# Item.net
KiCad netlist of a schematic drawn in Altium Designer
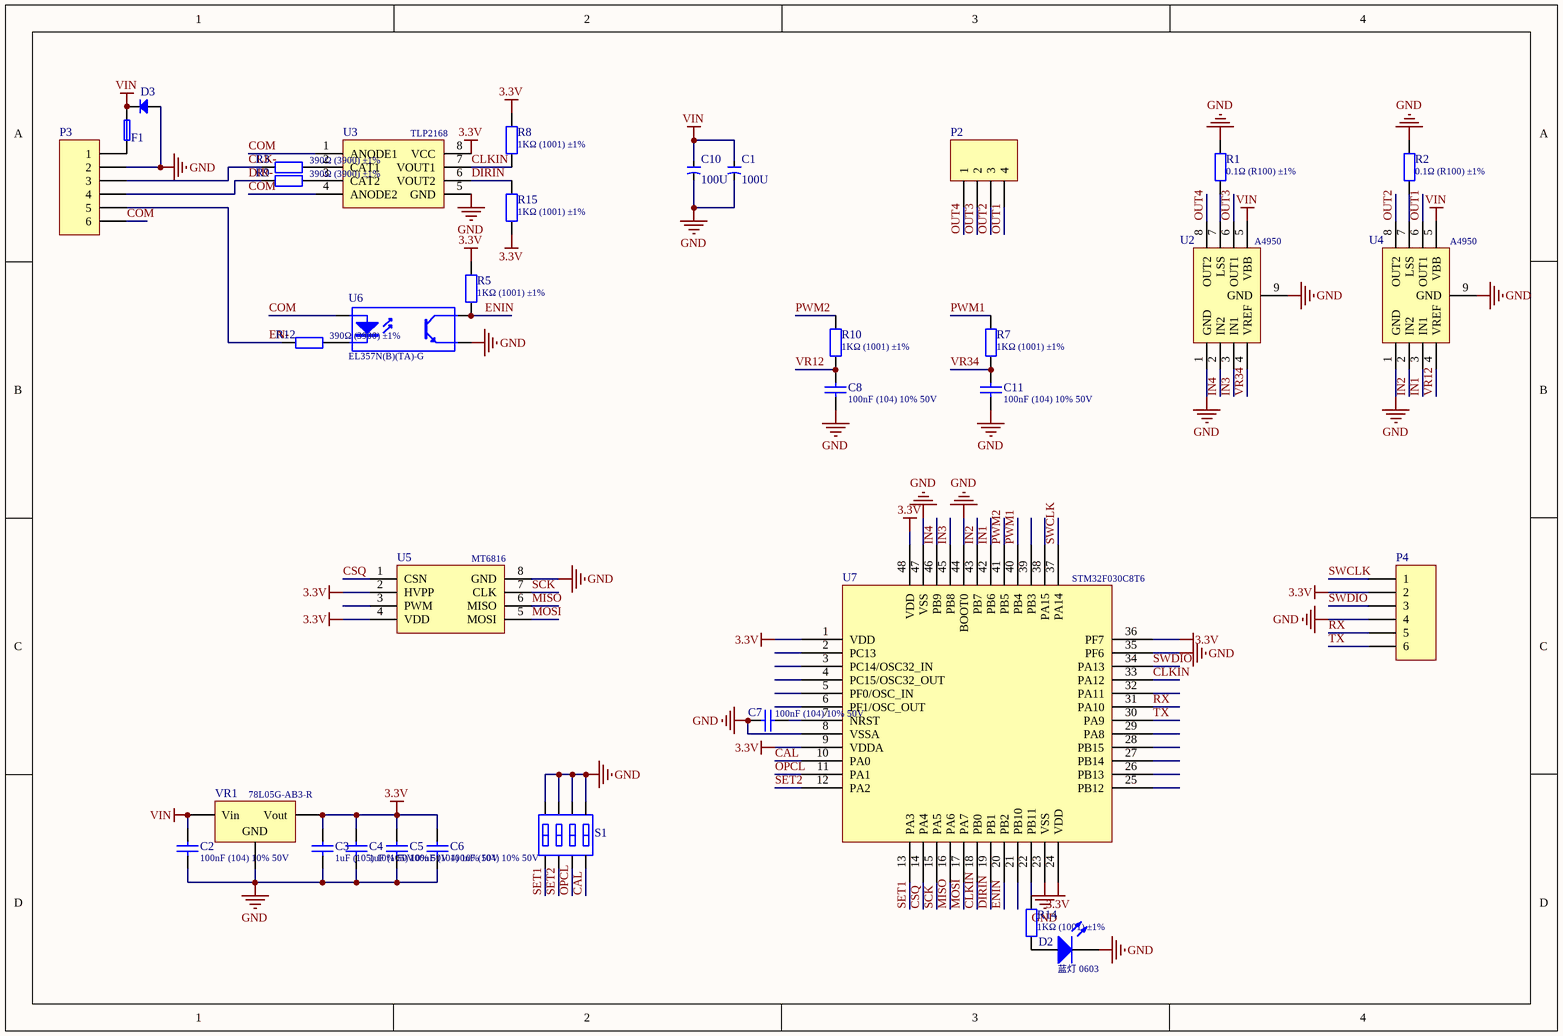
[diagram p0: Item.SchDoc]

(export (version "E")
  (design (tool "Eeschema 10.0.6"))
  (components
    (comp (ref "C1")
      (value "100U")
      (footprint "CAP6377")
      (description "Polarized Capacitor (Axial)")
      (fields (field (name "Comment") "CAP POL") (field (name "PUBLISHER") "Altium Limited"))
      (libsource (lib "MySchib") (part "CAP POL"))
    )
    (comp (ref "C2")
      (value "100nF (104) 10% 50V")
      (footprint "0603_C")
      (description "贴片电容")
      (libsource (lib "Miscellaneous Devices LC") (part "0603 100nF (104) 10% 50V"))
    )
    (comp (ref "C3")
      (value "1uF (105) 10% 50V")
      (footprint "0603_C")
      (description "贴片电容")
      (libsource (lib "Miscellaneous Devices LC") (part "0603 1uF (105) 10% 50V"))
    )
    (comp (ref "C4")
      (value "1uF (105) 10% 50V")
      (footprint "0603_C")
      (description "贴片电容")
      (libsource (lib "Miscellaneous Devices LC") (part "0603 1uF (105) 10% 50V"))
    )
    (comp (ref "C5")
      (value "100nF (104) 10% 50V")
      (footprint "0603_C")
      (description "贴片电容")
      (libsource (lib "Miscellaneous Devices LC") (part "0603 100nF (104) 10% 50V"))
    )
    (comp (ref "C6")
      (value "100nF (104) 10% 50V")
      (footprint "0603_C")
      (description "贴片电容")
      (libsource (lib "Miscellaneous Devices LC") (part "0603 100nF (104) 10% 50V"))
    )
    (comp (ref "C7")
      (value "100nF (104) 10% 50V")
      (footprint "0603_C")
      (description "贴片电容")
      (libsource (lib "Miscellaneous Devices LC") (part "0603 100nF (104) 10% 50V"))
    )
    (comp (ref "C8")
      (value "100nF (104) 10% 50V")
      (footprint "0603_C")
      (description "贴片电容")
      (libsource (lib "Miscellaneous Devices LC") (part "0603 100nF (104) 10% 50V"))
    )
    (comp (ref "C10")
      (value "100U")
      (footprint "CAP6377")
      (description "Polarized Capacitor (Axial)")
      (fields (field (name "Comment") "CAP POL") (field (name "PUBLISHER") "Altium Limited"))
      (libsource (lib "MySchib") (part "CAP POL"))
    )
    (comp (ref "C11")
      (value "100nF (104) 10% 50V")
      (footprint "0603_C")
      (description "贴片电容")
      (libsource (lib "Miscellaneous Devices LC") (part "0603 100nF (104) 10% 50V"))
    )
    (comp (ref "D2")
      (value "蓝灯 0603")
      (footprint "0603_LED_S1")
      (description "发光二极管")
      (libsource (lib "Miscellaneous Devices LC") (part "0603 蓝灯"))
    )
    (comp (ref "D3")
      (value "DIODE")
      (footprint "SOD-123")
      (description "Diode")
      (fields (field (name "PUBLISHER") "Altium Limited"))
      (libsource (lib "MySchib") (part "DIODE"))
    )
    (comp (ref "F1")
      (value "FUSE")
      (footprint "1206_R")
      (description "Fuse")
      (fields (field (name "PUBLISHER") "Altium Limited"))
      (libsource (lib "MySchib") (part "FUSE"))
    )
    (comp (ref "P2")
      (value "HEADER4")
      (footprint "XH-4-S-2")
      (description "Header, 4-Pin")
      (fields (field (name "PUBLISHER") "Altium Limited"))
      (libsource (lib "MySchib") (part "HEADER4"))
    )
    (comp (ref "P3")
      (value "HEADER6")
      (footprint "XH-6-S")
      (description "Header, 6-Pin")
      (fields (field (name "PUBLISHER") "Altium Limited"))
      (libsource (lib "MySchib") (part "HEADER6"))
    )
    (comp (ref "P4")
      (value "HEADER6")
      (footprint "6P-1.27MM")
      (description "Header, 6-Pin")
      (fields (field (name "PUBLISHER") "Altium Limited"))
      (libsource (lib "") (part "HEADER6_1"))
    )
    (comp (ref "R1")
      (value "0.1Ω (R100) ±1%")
      (footprint "1206_R")
      (description "贴片电阻")
      (libsource (lib "Miscellaneous Devices LC") (part "1206 0.1Ω (R100) 1%"))
    )
    (comp (ref "R2")
      (value "0.1Ω (R100) ±1%")
      (footprint "1206_R")
      (description "贴片电阻")
      (libsource (lib "Miscellaneous Devices LC") (part "1206 0.1Ω (R100) 1%"))
    )
    (comp (ref "R3")
      (value "390Ω (3900) ±1%")
      (footprint "0603_R")
      (description "贴片电阻")
      (libsource (lib "Miscellaneous Devices LC") (part "0603 390Ω (3900) 1%"))
    )
    (comp (ref "R5")
      (value "1KΩ (1001) ±1%")
      (footprint "0603_R")
      (description "贴片电阻")
      (libsource (lib "Miscellaneous Devices LC") (part "0603 1KΩ (1001) 1%"))
    )
    (comp (ref "R7")
      (value "1KΩ (1001) ±1%")
      (footprint "0603_R")
      (description "贴片电阻")
      (libsource (lib "Miscellaneous Devices LC") (part "0603 1KΩ (1001) 1%"))
    )
    (comp (ref "R8")
      (value "1KΩ (1001) ±1%")
      (footprint "0603_R")
      (description "贴片电阻")
      (libsource (lib "Miscellaneous Devices LC") (part "0603 1KΩ (1001) 1%"))
    )
    (comp (ref "R9")
      (value "390Ω (3900) ±1%")
      (footprint "0603_R")
      (description "贴片电阻")
      (libsource (lib "Miscellaneous Devices LC") (part "0603 390Ω (3900) 1%"))
    )
    (comp (ref "R10")
      (value "1KΩ (1001) ±1%")
      (footprint "0603_R")
      (description "贴片电阻")
      (libsource (lib "Miscellaneous Devices LC") (part "0603 1KΩ (1001) 1%"))
    )
    (comp (ref "R12")
      (value "390Ω (3900) ±1%")
      (footprint "0603_R")
      (description "贴片电阻")
      (libsource (lib "Miscellaneous Devices LC") (part "0603 390Ω (3900) 1%"))
    )
    (comp (ref "R14")
      (value "1KΩ (1001) ±1%")
      (footprint "0603_R")
      (description "贴片电阻")
      (libsource (lib "Miscellaneous Devices LC") (part "0603 1KΩ (1001) 1%"))
    )
    (comp (ref "R15")
      (value "1KΩ (1001) ±1%")
      (footprint "0603_R")
      (description "贴片电阻")
      (libsource (lib "Miscellaneous Devices LC") (part "0603 1KΩ (1001) 1%"))
    )
    (comp (ref "S1")
      (value "SWDIP-4")
      (footprint "SWSUR-4")
      (description "DIP Switch, 4Position, SPST")
      (fields (field (name "PUBLISHER") "Altium Limited"))
      (libsource (lib "MySchib") (part "SWDIP-4"))
    )
    (comp (ref "U2")
      (value "A4950")
      (footprint "SOIC-8_A4950")
      (description "Dual Full-Bridge  DMOS PWM Motor Driver")
      (libsource (lib "MySchib") (part "A4950"))
    )
    (comp (ref "U3")
      (value "TLP2168")
      (footprint "SO-8_3.9mm")
      (description "HIGH SPEED 10MBit/s LOGIC GATE  PHOTOCOUPLER")
      (libsource (lib "MySchib") (part "TLP2168"))
    )
    (comp (ref "U4")
      (value "A4950")
      (footprint "SOIC-8_A4950")
      (description "Dual Full-Bridge  DMOS PWM Motor Driver")
      (libsource (lib "MySchib") (part "A4950"))
    )
    (comp (ref "U5")
      (value "MT6816")
      (footprint "PG-DSO-8S")
      (description "GMR-Based Angle Sensor")
      (libsource (lib "MySchib") (part "MT6816"))
    )
    (comp (ref "U6")
      (value "EL357N(B)(TA)-G")
      (footprint "SOP-4_P2.54")
      (description "贴片光耦")
      (libsource (lib "Miscellaneous Devices LC") (part "EL357N(B)(TA)-G_[C6649]"))
    )
    (comp (ref "U7")
      (value "STM32F030C8T6")
      (footprint "LQFP-48_7x7x05P")
      (description "ARM")
      (libsource (lib "Miscellaneous Devices LC") (part "STM32F030C8T6"))
    )
    (comp (ref "VR1")
      (value "78L05G-AB3-R")
      (footprint "SOT-89(SOT-89-3)")
      (description "低压差线性稳压(LDO)")
      (libsource (lib "Miscellaneous Devices LC") (part "SOT-89 78L05G-AB3-R"))
    )
  )
  (nets
    (net (code "1") (name "/CAL") (class "Default")
      (node (ref "S1") (pin "7") (pinfunction "A4_7") (pintype "passive"))
      (node (ref "U7") (pin "10") (pinfunction "PA0_10") (pintype "passive"))
    )
    (net (code "2") (name "/CLK-") (class "Default")
      (node (ref "P3") (pin "3") (pinfunction "3_3") (pintype "passive"))
      (node (ref "R3") (pin "1") (pinfunction "1_1") (pintype "passive"))
    )
    (net (code "3") (name "/CLKIN") (class "Default")
      (node (ref "R8") (pin "1") (pinfunction "1_1") (pintype "passive"))
      (node (ref "U3") (pin "7") (pinfunction "VOUT1_7") (pintype "passive"))
      (node (ref "U7") (pin "18") (pinfunction "PB0_18") (pintype "passive"))
      (node (ref "U7") (pin "33") (pinfunction "PA12_33") (pintype "passive"))
    )
    (net (code "4") (name "/COM") (class "Default")
      (node (ref "P3") (pin "6") (pinfunction "6_6") (pintype "passive"))
      (node (ref "U3") (pin "1") (pinfunction "ANODE1_1") (pintype "passive"))
      (node (ref "U3") (pin "4") (pinfunction "ANODE2_4") (pintype "passive"))
      (node (ref "U6") (pin "1") (pinfunction "A_1") (pintype "passive"))
    )
    (net (code "5") (name "/CSQ") (class "Default")
      (node (ref "U5") (pin "1") (pinfunction "CSN_1") (pintype "passive"))
      (node (ref "U7") (pin "14") (pinfunction "PA4_14") (pintype "passive"))
    )
    (net (code "6") (name "/DIR-") (class "Default")
      (node (ref "P3") (pin "4") (pinfunction "4_4") (pintype "passive"))
      (node (ref "R9") (pin "1") (pinfunction "1_1") (pintype "passive"))
    )
    (net (code "7") (name "/DIRIN") (class "Default")
      (node (ref "R15") (pin "2") (pinfunction "2_2") (pintype "passive"))
      (node (ref "U3") (pin "6") (pinfunction "VOUT2_6") (pintype "passive"))
      (node (ref "U7") (pin "19") (pinfunction "PB1_19") (pintype "passive"))
    )
    (net (code "8") (name "/EN-") (class "Default")
      (node (ref "P3") (pin "5") (pinfunction "5_5") (pintype "passive"))
      (node (ref "R12") (pin "1") (pinfunction "1_1") (pintype "passive"))
    )
    (net (code "9") (name "/ENIN") (class "Default")
      (node (ref "R5") (pin "1") (pinfunction "1_1") (pintype "passive"))
      (node (ref "U6") (pin "4") (pinfunction "C_4") (pintype "passive"))
      (node (ref "U7") (pin "20") (pinfunction "PB2_20") (pintype "passive"))
    )
    (net (code "10") (name "/IN1") (class "Default")
      (node (ref "U4") (pin "3") (pinfunction "IN1_3") (pintype "passive"))
      (node (ref "U7") (pin "42") (pinfunction "PB6_42") (pintype "passive"))
    )
    (net (code "11") (name "/IN2") (class "Default")
      (node (ref "U4") (pin "2") (pinfunction "IN2_2") (pintype "passive"))
      (node (ref "U7") (pin "43") (pinfunction "PB7_43") (pintype "passive"))
    )
    (net (code "12") (name "/IN3") (class "Default")
      (node (ref "U2") (pin "3") (pinfunction "IN1_3") (pintype "passive"))
      (node (ref "U7") (pin "45") (pinfunction "PB8_45") (pintype "passive"))
    )
    (net (code "13") (name "/IN4") (class "Default")
      (node (ref "U2") (pin "2") (pinfunction "IN2_2") (pintype "passive"))
      (node (ref "U7") (pin "46") (pinfunction "PB9_46") (pintype "passive"))
    )
    (net (code "14") (name "/MISO") (class "Default")
      (node (ref "U5") (pin "6") (pinfunction "MISO_6") (pintype "passive"))
      (node (ref "U7") (pin "16") (pinfunction "PA6_16") (pintype "passive"))
    )
    (net (code "15") (name "/MOSI") (class "Default")
      (node (ref "U5") (pin "5") (pinfunction "MOSI_5") (pintype "passive"))
      (node (ref "U7") (pin "17") (pinfunction "PA7_17") (pintype "passive"))
    )
    (net (code "16") (name "/OPCL") (class "Default")
      (node (ref "S1") (pin "5") (pinfunction "A3_5") (pintype "passive"))
      (node (ref "U7") (pin "11") (pinfunction "PA1_11") (pintype "passive"))
    )
    (net (code "17") (name "/OUT1") (class "Default")
      (node (ref "P2") (pin "4") (pinfunction "4_4") (pintype "passive"))
      (node (ref "U4") (pin "6") (pinfunction "OUT1_6") (pintype "passive"))
    )
    (net (code "18") (name "/OUT2") (class "Default")
      (node (ref "P2") (pin "3") (pinfunction "3_3") (pintype "passive"))
      (node (ref "U4") (pin "8") (pinfunction "OUT2_8") (pintype "passive"))
    )
    (net (code "19") (name "/OUT3") (class "Default")
      (node (ref "P2") (pin "2") (pinfunction "2_2") (pintype "passive"))
      (node (ref "U2") (pin "6") (pinfunction "OUT1_6") (pintype "passive"))
    )
    (net (code "20") (name "/OUT4") (class "Default")
      (node (ref "P2") (pin "1") (pinfunction "1_1") (pintype "passive"))
      (node (ref "U2") (pin "8") (pinfunction "OUT2_8") (pintype "passive"))
    )
    (net (code "21") (name "/PWM1") (class "Default")
      (node (ref "R7") (pin "2") (pinfunction "2_2") (pintype "passive"))
      (node (ref "U7") (pin "40") (pinfunction "PB4_40") (pintype "passive"))
    )
    (net (code "22") (name "/PWM2") (class "Default")
      (node (ref "R10") (pin "2") (pinfunction "2_2") (pintype "passive"))
      (node (ref "U7") (pin "41") (pinfunction "PB5_41") (pintype "passive"))
    )
    (net (code "23") (name "/RX") (class "Default")
      (node (ref "P4") (pin "5") (pinfunction "5_5") (pintype "passive"))
      (node (ref "U7") (pin "31") (pinfunction "PA10_31") (pintype "passive"))
    )
    (net (code "24") (name "/SCK") (class "Default")
      (node (ref "U5") (pin "7") (pinfunction "CLK_7") (pintype "passive"))
      (node (ref "U7") (pin "15") (pinfunction "PA5_15") (pintype "passive"))
    )
    (net (code "25") (name "/SET1") (class "Default")
      (node (ref "S1") (pin "1") (pinfunction "A1_1") (pintype "passive"))
      (node (ref "U7") (pin "13") (pinfunction "PA3_13") (pintype "passive"))
    )
    (net (code "26") (name "/SET2") (class "Default")
      (node (ref "S1") (pin "3") (pinfunction "A2_3") (pintype "passive"))
      (node (ref "U7") (pin "12") (pinfunction "PA2_12") (pintype "passive"))
    )
    (net (code "27") (name "/SWCLK") (class "Default")
      (node (ref "P4") (pin "1") (pinfunction "1_1") (pintype "passive"))
      (node (ref "U7") (pin "37") (pinfunction "PA14_37") (pintype "passive"))
    )
    (net (code "28") (name "/SWDIO") (class "Default")
      (node (ref "P4") (pin "3") (pinfunction "3_3") (pintype "passive"))
      (node (ref "U7") (pin "34") (pinfunction "PA13_34") (pintype "passive"))
    )
    (net (code "29") (name "/TX") (class "Default")
      (node (ref "P4") (pin "6") (pinfunction "6_6") (pintype "passive"))
      (node (ref "U7") (pin "30") (pinfunction "PA9_30") (pintype "passive"))
    )
    (net (code "30") (name "/VR12") (class "Default")
      (node (ref "C8") (pin "2") (pinfunction "2_2") (pintype "passive"))
      (node (ref "R10") (pin "1") (pinfunction "1_1") (pintype "passive"))
      (node (ref "U4") (pin "4") (pinfunction "VREF_4") (pintype "passive"))
    )
    (net (code "31") (name "/VR34") (class "Default")
      (node (ref "C11") (pin "2") (pinfunction "2_2") (pintype "passive"))
      (node (ref "R7") (pin "1") (pinfunction "1_1") (pintype "passive"))
      (node (ref "U2") (pin "4") (pinfunction "VREF_4") (pintype "passive"))
    )
    (net (code "32") (name "3.3V") (class "Default")
      (node (ref "C3") (pin "2") (pinfunction "2_2") (pintype "passive"))
      (node (ref "C4") (pin "2") (pinfunction "2_2") (pintype "passive"))
      (node (ref "C5") (pin "1") (pinfunction "1_1") (pintype "passive"))
      (node (ref "C6") (pin "1") (pinfunction "1_1") (pintype "passive"))
      (node (ref "P4") (pin "2") (pinfunction "2_2") (pintype "passive"))
      (node (ref "R15") (pin "1") (pinfunction "1_1") (pintype "passive"))
      (node (ref "R5") (pin "2") (pinfunction "2_2") (pintype "passive"))
      (node (ref "R8") (pin "2") (pinfunction "2_2") (pintype "passive"))
      (node (ref "U3") (pin "8") (pinfunction "VCC_8") (pintype "passive"))
      (node (ref "U5") (pin "2") (pinfunction "HVPP_2") (pintype "passive"))
      (node (ref "U5") (pin "4") (pinfunction "VDD_4") (pintype "passive"))
      (node (ref "U7") (pin "1") (pinfunction "VDD_1") (pintype "passive"))
      (node (ref "U7") (pin "24") (pinfunction "VDD_24") (pintype "passive"))
      (node (ref "U7") (pin "36") (pinfunction "PF7_36") (pintype "passive"))
      (node (ref "U7") (pin "48") (pinfunction "VDD_48") (pintype "passive"))
      (node (ref "U7") (pin "9") (pinfunction "VDDA_9") (pintype "passive"))
      (node (ref "VR1") (pin "1") (pinfunction "Vout_1") (pintype "passive"))
    )
    (net (code "33") (name "GND") (class "Default")
      (node (ref "C1") (pin "2") (pinfunction "2_2") (pintype "passive"))
      (node (ref "C10") (pin "2") (pinfunction "2_2") (pintype "passive"))
      (node (ref "C11") (pin "1") (pinfunction "1_1") (pintype "passive"))
      (node (ref "C2") (pin "2") (pinfunction "2_2") (pintype "passive"))
      (node (ref "C3") (pin "1") (pinfunction "1_1") (pintype "passive"))
      (node (ref "C4") (pin "1") (pinfunction "1_1") (pintype "passive"))
      (node (ref "C5") (pin "2") (pinfunction "2_2") (pintype "passive"))
      (node (ref "C6") (pin "2") (pinfunction "2_2") (pintype "passive"))
      (node (ref "C7") (pin "2") (pinfunction "2_2") (pintype "passive"))
      (node (ref "C8") (pin "1") (pinfunction "1_1") (pintype "passive"))
      (node (ref "D2") (pin "K") (pinfunction "K_K") (pintype "passive"))
      (node (ref "D3") (pin "1") (pinfunction "A_1") (pintype "passive"))
      (node (ref "P3") (pin "2") (pinfunction "2_2") (pintype "passive"))
      (node (ref "P4") (pin "4") (pinfunction "4_4") (pintype "passive"))
      (node (ref "R1") (pin "1") (pinfunction "1_1") (pintype "passive"))
      (node (ref "R2") (pin "1") (pinfunction "1_1") (pintype "passive"))
      (node (ref "S1") (pin "2") (pinfunction "B1_2") (pintype "passive"))
      (node (ref "S1") (pin "4") (pinfunction "B2_4") (pintype "passive"))
      (node (ref "S1") (pin "6") (pinfunction "B3_6") (pintype "passive"))
      (node (ref "S1") (pin "8") (pinfunction "B4_8") (pintype "passive"))
      (node (ref "U2") (pin "1") (pinfunction "GND_1") (pintype "passive"))
      (node (ref "U2") (pin "9") (pinfunction "GND_9") (pintype "passive"))
      (node (ref "U3") (pin "5") (pinfunction "GND_5") (pintype "passive"))
      (node (ref "U4") (pin "1") (pinfunction "GND_1") (pintype "passive"))
      (node (ref "U4") (pin "9") (pinfunction "GND_9") (pintype "passive"))
      (node (ref "U5") (pin "8") (pinfunction "GND_8") (pintype "passive"))
      (node (ref "U6") (pin "3") (pinfunction "E_3") (pintype "passive"))
      (node (ref "U7") (pin "23") (pinfunction "VSS_23") (pintype "passive"))
      (node (ref "U7") (pin "35") (pinfunction "PF6_35") (pintype "passive"))
      (node (ref "U7") (pin "44") (pinfunction "BOOT0_44") (pintype "passive"))
      (node (ref "U7") (pin "47") (pinfunction "VSS_47") (pintype "passive"))
      (node (ref "U7") (pin "8") (pinfunction "VSSA_8") (pintype "passive"))
      (node (ref "VR1") (pin "2") (pinfunction "GND_2") (pintype "passive"))
    )
    (net (code "34") (name "Net-(D2-PadA)") (class "Default")
      (node (ref "D2") (pin "A") (pinfunction "A_A") (pintype "passive"))
      (node (ref "R14") (pin "1") (pinfunction "1_1") (pintype "passive"))
    )
    (net (code "35") (name "Net-(F1-Pad1)") (class "Default")
      (node (ref "F1") (pin "1") (pinfunction "1_1") (pintype "passive"))
      (node (ref "P3") (pin "1") (pinfunction "1_1") (pintype "passive"))
    )
    (net (code "36") (name "Net-(U2-LSS)") (class "Default")
      (node (ref "R1") (pin "2") (pinfunction "2_2") (pintype "passive"))
      (node (ref "U2") (pin "7") (pinfunction "LSS_7") (pintype "passive"))
    )
    (net (code "37") (name "Net-(U3-CAT1)") (class "Default")
      (node (ref "R3") (pin "2") (pinfunction "2_2") (pintype "passive"))
      (node (ref "U3") (pin "2") (pinfunction "CAT1_2") (pintype "passive"))
    )
    (net (code "38") (name "Net-(U3-CAT2)") (class "Default")
      (node (ref "R9") (pin "2") (pinfunction "2_2") (pintype "passive"))
      (node (ref "U3") (pin "3") (pinfunction "CAT2_3") (pintype "passive"))
    )
    (net (code "39") (name "Net-(U4-LSS)") (class "Default")
      (node (ref "R2") (pin "2") (pinfunction "2_2") (pintype "passive"))
      (node (ref "U4") (pin "7") (pinfunction "LSS_7") (pintype "passive"))
    )
    (net (code "40") (name "Net-(U6-K)") (class "Default")
      (node (ref "R12") (pin "2") (pinfunction "2_2") (pintype "passive"))
      (node (ref "U6") (pin "2") (pinfunction "K_2") (pintype "passive"))
    )
    (net (code "41") (name "Net-(U7-NRST)") (class "Default")
      (node (ref "C7") (pin "1") (pinfunction "1_1") (pintype "passive"))
      (node (ref "U7") (pin "7") (pinfunction "NRST_7") (pintype "passive"))
    )
    (net (code "42") (name "Net-(U7-PB11)") (class "Default")
      (node (ref "R14") (pin "2") (pinfunction "2_2") (pintype "passive"))
      (node (ref "U7") (pin "22") (pinfunction "PB11_22") (pintype "passive"))
    )
    (net (code "43") (name "VIN") (class "Default")
      (node (ref "C1") (pin "1") (pinfunction "1_1") (pintype "passive"))
      (node (ref "C10") (pin "1") (pinfunction "1_1") (pintype "passive"))
      (node (ref "C2") (pin "1") (pinfunction "1_1") (pintype "passive"))
      (node (ref "D3") (pin "2") (pinfunction "K_2") (pintype "passive"))
      (node (ref "F1") (pin "2") (pinfunction "2_2") (pintype "passive"))
      (node (ref "U2") (pin "5") (pinfunction "VBB_5") (pintype "passive"))
      (node (ref "U4") (pin "5") (pinfunction "VBB_5") (pintype "passive"))
      (node (ref "VR1") (pin "3") (pinfunction "Vin_3") (pintype "passive"))
    )
    (net (code "44") (name "unconnected-(U5-PWM-Pad3)") (class "Default")
      (node (ref "U5") (pin "3") (pinfunction "PWM_3") (pintype "passive"))
    )
    (net (code "45") (name "unconnected-(U7-PA8-Pad29)") (class "Default")
      (node (ref "U7") (pin "29") (pinfunction "PA8_29") (pintype "passive"))
    )
    (net (code "46") (name "unconnected-(U7-PA11-Pad32)") (class "Default")
      (node (ref "U7") (pin "32") (pinfunction "PA11_32") (pintype "passive"))
    )
    (net (code "47") (name "unconnected-(U7-PA15-Pad38)") (class "Default")
      (node (ref "U7") (pin "38") (pinfunction "PA15_38") (pintype "passive"))
    )
    (net (code "48") (name "unconnected-(U7-PB3-Pad39)") (class "Default")
      (node (ref "U7") (pin "39") (pinfunction "PB3_39") (pintype "passive"))
    )
    (net (code "49") (name "unconnected-(U7-PB10-Pad21)") (class "Default")
      (node (ref "U7") (pin "21") (pinfunction "PB10_21") (pintype "passive"))
    )
    (net (code "50") (name "unconnected-(U7-PB12-Pad25)") (class "Default")
      (node (ref "U7") (pin "25") (pinfunction "PB12_25") (pintype "passive"))
    )
    (net (code "51") (name "unconnected-(U7-PB13-Pad26)") (class "Default")
      (node (ref "U7") (pin "26") (pinfunction "PB13_26") (pintype "passive"))
    )
    (net (code "52") (name "unconnected-(U7-PB14-Pad27)") (class "Default")
      (node (ref "U7") (pin "27") (pinfunction "PB14_27") (pintype "passive"))
    )
    (net (code "53") (name "unconnected-(U7-PB15-Pad28)") (class "Default")
      (node (ref "U7") (pin "28") (pinfunction "PB15_28") (pintype "passive"))
    )
    (net (code "54") (name "unconnected-(U7-PC13-Pad2)") (class "Default")
      (node (ref "U7") (pin "2") (pinfunction "PC13_2") (pintype "passive"))
    )
    (net (code "55") (name "unconnected-(U7-PC14{slash}OSC32_IN-Pad3)") (class "Default")
      (node (ref "U7") (pin "3") (pinfunction "PC14/OSC32_IN_3") (pintype "passive"))
    )
    (net (code "56") (name "unconnected-(U7-PC15{slash}OSC32_OUT-Pad4)") (class "Default")
      (node (ref "U7") (pin "4") (pinfunction "PC15/OSC32_OUT_4") (pintype "passive"))
    )
    (net (code "57") (name "unconnected-(U7-PF0{slash}OSC_IN-Pad5)") (class "Default")
      (node (ref "U7") (pin "5") (pinfunction "PF0/OSC_IN_5") (pintype "passive"))
    )
    (net (code "58") (name "unconnected-(U7-PF1{slash}OSC_OUT-Pad6)") (class "Default")
      (node (ref "U7") (pin "6") (pinfunction "PF1/OSC_OUT_6") (pintype "passive"))
    )
  )
)
